# RS232.net
KiCad netlist of a schematic drawn in Altium Designer
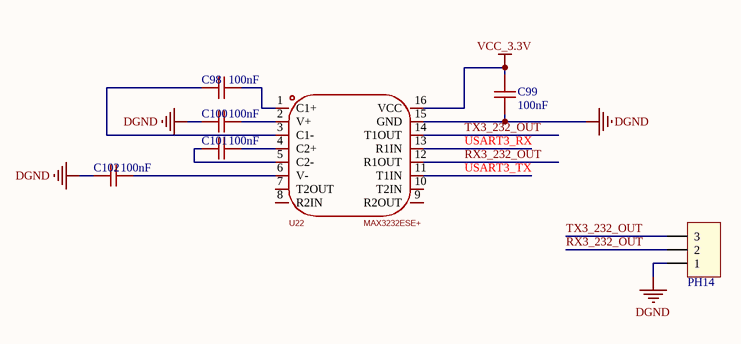
[diagram p0: RS232.SchDoc]

(export (version "E")
  (design (tool "Eeschema 10.0.6"))
  (components
    (comp (ref "C98")
      (value "100nF")
      (footprint "C0603")
      (description "贴片电容,X7R")
      (libsource (lib "XG_DW_POCT_2K10LED_3") (part "100nF/50V,C0603"))
    )
    (comp (ref "C99")
      (value "100nF")
      (footprint "C0603")
      (description "贴片电容,X7R")
      (libsource (lib "XG_DW_POCT_2K10LED_3") (part "100nF/50V,C0603"))
    )
    (comp (ref "C100")
      (value "100nF")
      (footprint "C0603")
      (description "贴片电容,X7R")
      (libsource (lib "XG_DW_POCT_2K10LED_3") (part "100nF/50V,C0603"))
    )
    (comp (ref "C101")
      (value "100nF")
      (footprint "C0603")
      (description "贴片电容,X7R")
      (libsource (lib "XG_DW_POCT_2K10LED_3") (part "100nF/50V,C0603"))
    )
    (comp (ref "C102")
      (value "100nF")
      (footprint "C0603")
      (description "贴片电容,X7R")
      (libsource (lib "XG_DW_POCT_2K10LED_3") (part "100nF/50V,C0603"))
    )
    (comp (ref "PH14")
      (value "PH2.0-3P")
      (footprint "PH2.0-3P 弯针")
      (libsource (lib "XG_DW_POCT_2K10LED_3") (part "PH2.0-3P"))
    )
    (comp (ref "U22")
      (value "MAX3232ESE+")
      (footprint "SOIC-16_L9.9-W3.9-P1.27-LS6.0-BL")
      (fields (field (name "MANUFACTURER") "ADI(亚德诺)/MAXIM(美信)"))
      (libsource (lib "XG_DW_POCT_2K10LED_3") (part "MAX3232ESE+"))
    )
  )
  (nets
    (net (code "1") (name "/RX3_232_OUT") (class "Default")
      (node (ref "PH14") (pin "2") (pinfunction "2_2") (pintype "passive"))
      (node (ref "U22") (pin "12") (pinfunction "R1OUT_12") (pintype "passive"))
    )
    (net (code "2") (name "/TX3_232_OUT") (class "Default")
      (node (ref "PH14") (pin "3") (pinfunction "3_3") (pintype "passive"))
      (node (ref "U22") (pin "14") (pinfunction "T1OUT_14") (pintype "passive"))
    )
    (net (code "3") (name "/USART3_RX") (class "Default")
      (node (ref "U22") (pin "13") (pinfunction "R1IN_13") (pintype "passive"))
    )
    (net (code "4") (name "/USART3_TX") (class "Default")
      (node (ref "U22") (pin "11") (pinfunction "T1IN_11") (pintype "passive"))
    )
    (net (code "5") (name "DGND") (class "Default")
      (node (ref "C100") (pin "2") (pinfunction "2_2") (pintype "passive"))
      (node (ref "C102") (pin "2") (pinfunction "2_2") (pintype "passive"))
      (node (ref "C99") (pin "1") (pinfunction "1_1") (pintype "passive"))
      (node (ref "PH14") (pin "1") (pinfunction "1_1") (pintype "passive"))
      (node (ref "U22") (pin "15") (pinfunction "GND_15") (pintype "passive"))
    )
    (net (code "6") (name "Net-(U22-C1+)") (class "Default")
      (node (ref "C98") (pin "1") (pinfunction "1_1") (pintype "passive"))
      (node (ref "U22") (pin "1") (pinfunction "C1+_1") (pintype "passive"))
    )
    (net (code "7") (name "Net-(U22-C1-)") (class "Default")
      (node (ref "C98") (pin "2") (pinfunction "2_2") (pintype "passive"))
      (node (ref "U22") (pin "3") (pinfunction "C1-_3") (pintype "passive"))
    )
    (net (code "8") (name "Net-(U22-C2+)") (class "Default")
      (node (ref "C101") (pin "1") (pinfunction "1_1") (pintype "passive"))
      (node (ref "U22") (pin "4") (pinfunction "C2+_4") (pintype "passive"))
    )
    (net (code "9") (name "Net-(U22-C2-)") (class "Default")
      (node (ref "C101") (pin "2") (pinfunction "2_2") (pintype "passive"))
      (node (ref "U22") (pin "5") (pinfunction "C2-_5") (pintype "passive"))
    )
    (net (code "10") (name "Net-(U22-V+)") (class "Default")
      (node (ref "C100") (pin "1") (pinfunction "1_1") (pintype "passive"))
      (node (ref "U22") (pin "2") (pinfunction "V+_2") (pintype "passive"))
    )
    (net (code "11") (name "Net-(U22-V-)") (class "Default")
      (node (ref "C102") (pin "1") (pinfunction "1_1") (pintype "passive"))
      (node (ref "U22") (pin "6") (pinfunction "V-_6") (pintype "passive"))
    )
    (net (code "12") (name "VCC_3.3V") (class "Default")
      (node (ref "C99") (pin "2") (pinfunction "2_2") (pintype "passive"))
      (node (ref "U22") (pin "16") (pinfunction "VCC_16") (pintype "passive"))
    )
    (net (code "13") (name "unconnected-(U22-R2IN-Pad8)") (class "Default")
      (node (ref "U22") (pin "8") (pinfunction "R2IN_8") (pintype "passive"))
    )
    (net (code "14") (name "unconnected-(U22-R2OUT-Pad9)") (class "Default")
      (node (ref "U22") (pin "9") (pinfunction "R2OUT_9") (pintype "passive"))
    )
    (net (code "15") (name "unconnected-(U22-T2IN-Pad10)") (class "Default")
      (node (ref "U22") (pin "10") (pinfunction "T2IN_10") (pintype "passive"))
    )
    (net (code "16") (name "unconnected-(U22-T2OUT-Pad7)") (class "Default")
      (node (ref "U22") (pin "7") (pinfunction "T2OUT_7") (pintype "passive"))
    )
  )
)
